# sensors1.net
KiCad netlist of a schematic drawn in EAGLE
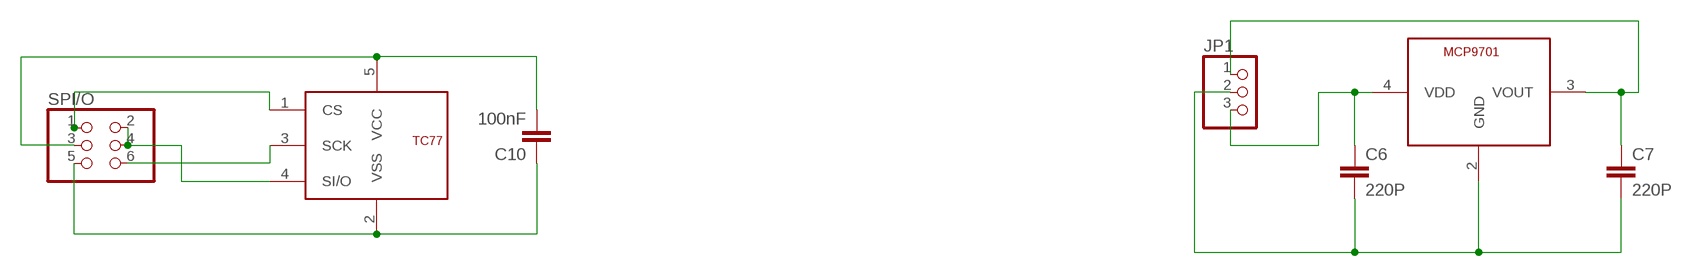
[diagram p0: schematic, sheet 1]

(export (version "E")
  (design (tool "Eeschema 10.0.6"))
  (components
    (comp (ref "C6")
      (value "220P")
      (footprint "eagle-import:C0805")
      (libsource (lib "eagle-import") (part "C-EUC0805"))
    )
    (comp (ref "C7")
      (value "220P")
      (footprint "eagle-import:C0805")
      (libsource (lib "eagle-import") (part "C-EUC0805"))
    )
    (comp (ref "C10")
      (value "100nF")
      (footprint "eagle-import:C0805K")
      (libsource (lib "eagle-import") (part "C-EUC0805K"))
    )
    (comp (ref "JP1")
      (value "PINHD-1X3")
      (footprint "eagle-import:1X03")
      (libsource (lib "eagle-import") (part "PINHD-1X3"))
    )
    (comp (ref "SPI/O")
      (value "PINHD-2X3")
      (footprint "eagle-import:2X03")
      (libsource (lib "eagle-import") (part "PINHD-2X3"))
    )
    (comp (ref "U$1")
      (value "MCP9701")
      (footprint "eagle-import:SC70-5L")
      (libsource (lib "eagle-import") (part "MCP9701"))
    )
    (comp (ref "U$5")
      (value "TC77-3.3MCTTR")
      (footprint "eagle-import:SOT23-5")
      (libsource (lib "eagle-import") (part "TC77-3.3MCTTR"))
    )
  )
  (nets
    (net (code "1") (name "Net-(U$1-GND)") (class "Default")
      (node (ref "C6") (pin "2") (pinfunction "2_2") (pintype "passive"))
      (node (ref "C7") (pin "2") (pinfunction "2_2") (pintype "passive"))
      (node (ref "JP1") (pin "2") (pinfunction "2_2") (pintype "passive"))
      (node (ref "U$1") (pin "2") (pinfunction "GND_2") (pintype "bidirectional"))
    )
    (net (code "2") (name "Net-(U$1-VDD)") (class "Default")
      (node (ref "C6") (pin "1") (pinfunction "1_1") (pintype "passive"))
      (node (ref "JP1") (pin "3") (pinfunction "3_3") (pintype "passive"))
      (node (ref "U$1") (pin "4") (pinfunction "VDD_4") (pintype "bidirectional"))
    )
    (net (code "3") (name "Net-(U$1-VOUT)") (class "Default")
      (node (ref "C7") (pin "1") (pinfunction "1_1") (pintype "passive"))
      (node (ref "JP1") (pin "1") (pinfunction "1_1") (pintype "passive"))
      (node (ref "U$1") (pin "3") (pinfunction "VOUT_3") (pintype "bidirectional"))
    )
    (net (code "4") (name "Net-(U$5-CS)") (class "Default")
      (node (ref "SPI/O") (pin "1") (pinfunction "1_1") (pintype "passive"))
      (node (ref "U$5") (pin "1") (pinfunction "CS_1") (pintype "bidirectional"))
    )
    (net (code "5") (name "Net-(U$5-SCK)") (class "Default")
      (node (ref "SPI/O") (pin "6") (pinfunction "6_6") (pintype "passive"))
      (node (ref "U$5") (pin "3") (pinfunction "SCK_3") (pintype "bidirectional"))
    )
    (net (code "6") (name "Net-(U$5-SI{slash}O)") (class "Default")
      (node (ref "SPI/O") (pin "2") (pinfunction "2_2") (pintype "passive"))
      (node (ref "SPI/O") (pin "4") (pinfunction "4_4") (pintype "passive"))
      (node (ref "U$5") (pin "4") (pinfunction "SI/O_4") (pintype "bidirectional"))
    )
    (net (code "7") (name "Net-(U$5-VCC)") (class "Default")
      (node (ref "C10") (pin "2") (pinfunction "2_2") (pintype "passive"))
      (node (ref "SPI/O") (pin "3") (pinfunction "3_3") (pintype "passive"))
      (node (ref "U$5") (pin "5") (pinfunction "VCC_5") (pintype "bidirectional"))
    )
    (net (code "8") (name "Net-(U$5-VSS)") (class "Default")
      (node (ref "C10") (pin "1") (pinfunction "1_1") (pintype "passive"))
      (node (ref "SPI/O") (pin "5") (pinfunction "5_5") (pintype "passive"))
      (node (ref "U$5") (pin "2") (pinfunction "VSS_2") (pintype "bidirectional"))
    )
  )
)
